# mk3-schield-samtec-vias.net
KiCad netlist of a schematic drawn in EAGLE
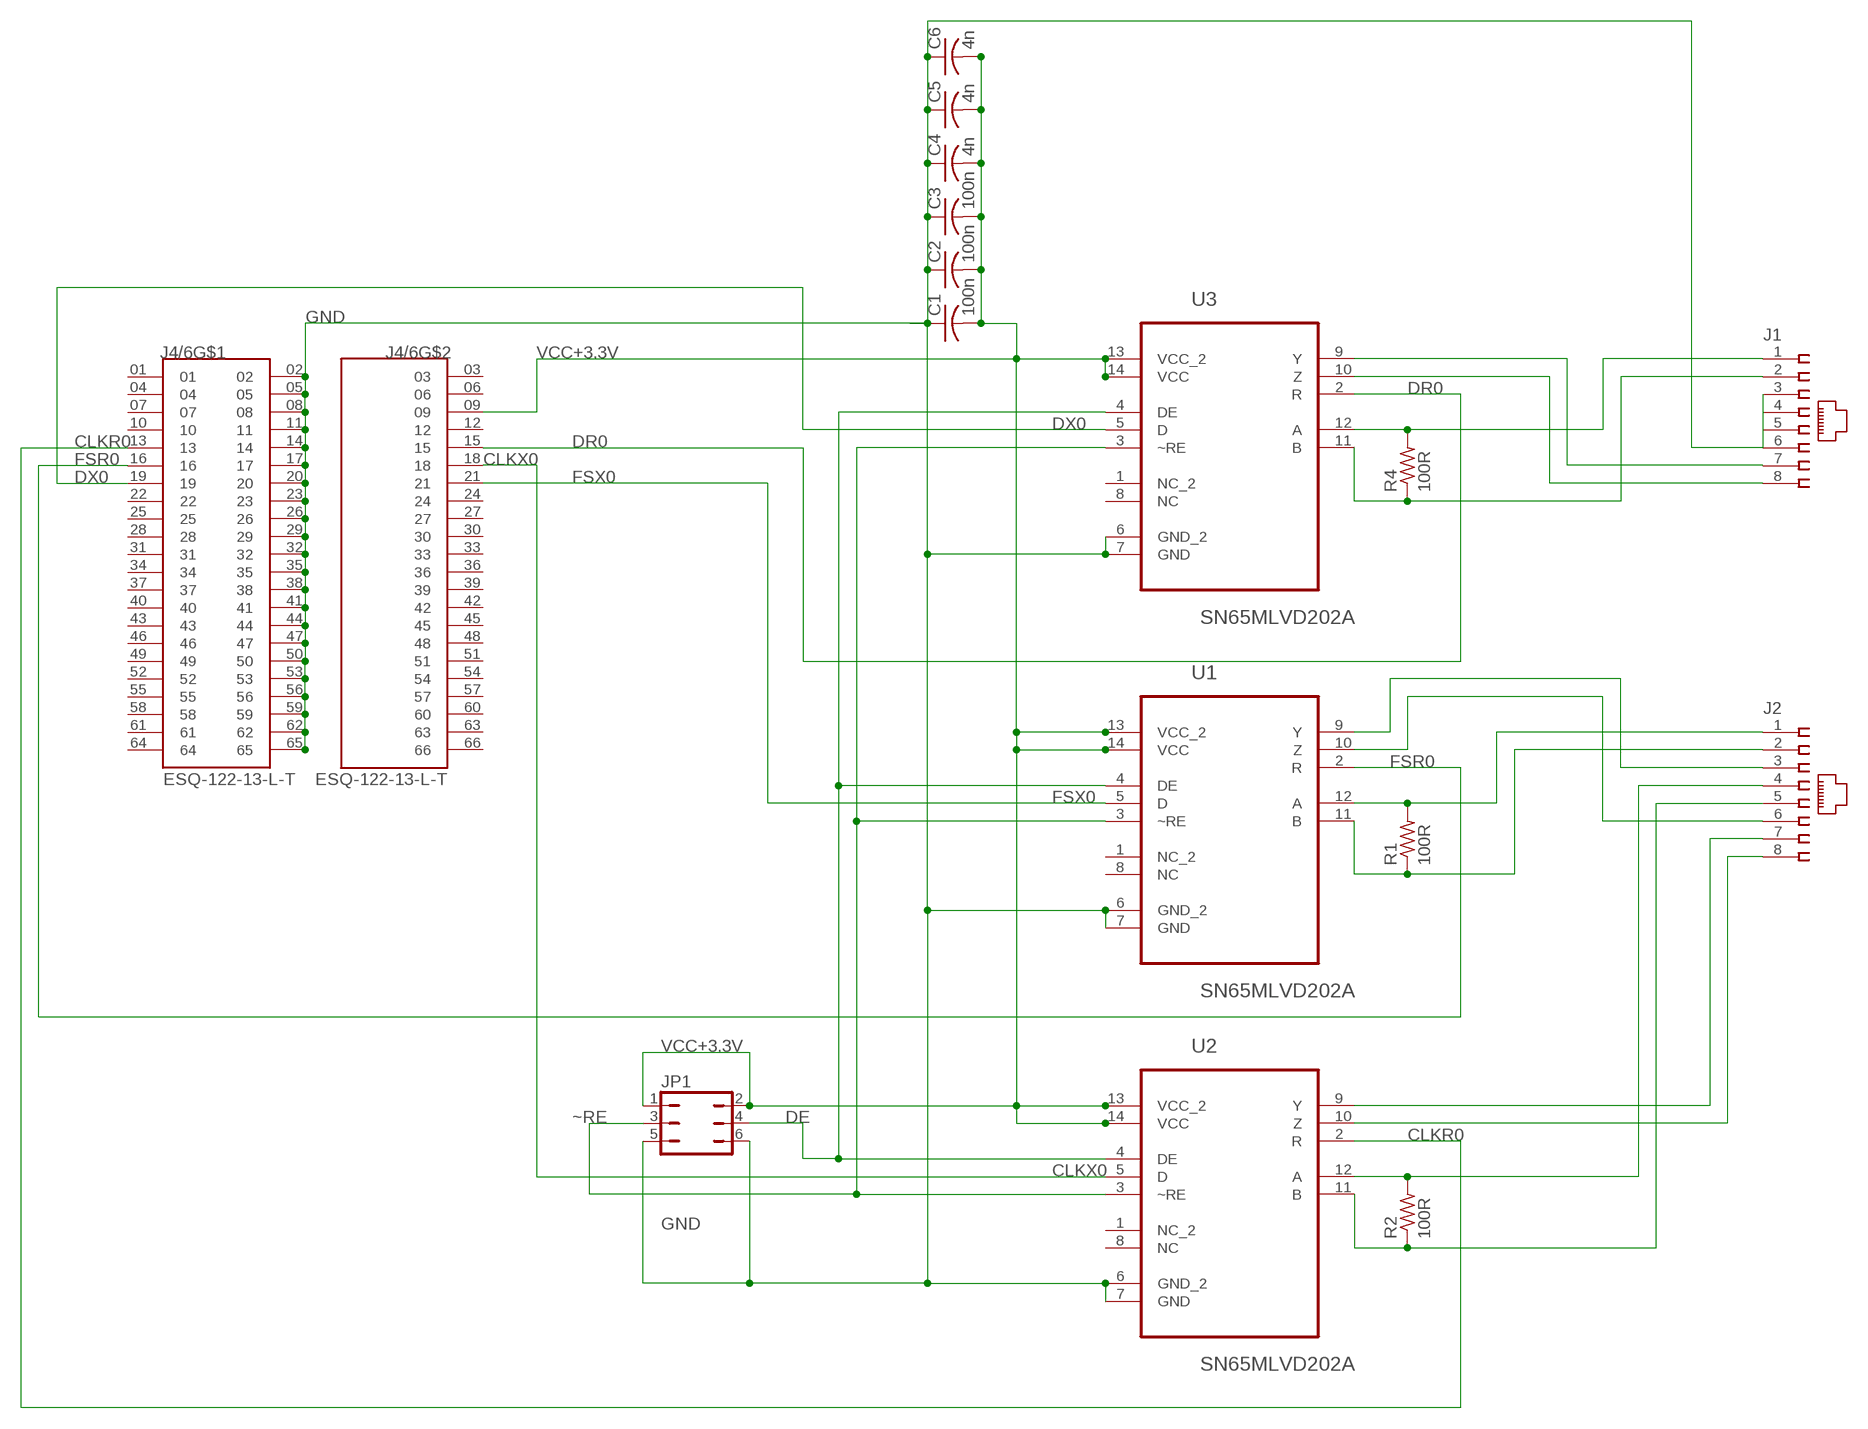
[diagram p0: schematic, sheet 1]

(export (version "E")
  (design (tool "Eeschema 10.0.6"))
  (components
    (comp (ref "C1")
      (value "100n")
      (footprint "eagle-import:C0805")
      (libsource (lib "eagle-import") (part "C-USC0805"))
    )
    (comp (ref "C2")
      (value "100n")
      (footprint "eagle-import:C0805")
      (libsource (lib "eagle-import") (part "C-USC0805"))
    )
    (comp (ref "C3")
      (value "100n")
      (footprint "eagle-import:C0805")
      (libsource (lib "eagle-import") (part "C-USC0805"))
    )
    (comp (ref "C4")
      (value "4n")
      (footprint "eagle-import:C0805")
      (libsource (lib "eagle-import") (part "C-USC0805"))
    )
    (comp (ref "C5")
      (value "4n")
      (footprint "eagle-import:C0805")
      (libsource (lib "eagle-import") (part "C-USC0805"))
    )
    (comp (ref "C6")
      (value "4n")
      (footprint "eagle-import:C0805")
      (libsource (lib "eagle-import") (part "C-USC0805"))
    )
    (comp (ref "J1")
      (value "557785-1-SHIELD")
      (footprint "eagle-import:557785-1")
      (libsource (lib "eagle-import") (part "557785-1-SHIELD"))
    )
    (comp (ref "J2")
      (value "557785-1-SHIELD")
      (footprint "eagle-import:557785-1")
      (libsource (lib "eagle-import") (part "557785-1-SHIELD"))
    )
    (comp (ref "J4/6")
      (value "ESQ-122-13-L-T")
      (footprint "eagle-import:SAMTEC_ESQ-122-13-L-T")
      (fields (field (name "MANUFACTURER") "Samtec"))
      (libsource (lib "eagle-import") (part "ESQ-122-13-L-T"))
    )
    (comp (ref "JP1")
      (value "JP3Q")
      (footprint "eagle-import:JP3Q")
      (libsource (lib "eagle-import") (part "JP3Q"))
    )
    (comp (ref "R1")
      (value "100R")
      (footprint "eagle-import:R0402")
      (libsource (lib "eagle-import") (part "R-US_R0402"))
    )
    (comp (ref "R2")
      (value "100R")
      (footprint "eagle-import:R0402")
      (libsource (lib "eagle-import") (part "R-US_R0402"))
    )
    (comp (ref "R4")
      (value "100R")
      (footprint "eagle-import:R0402")
      (libsource (lib "eagle-import") (part "R-US_R0402"))
    )
    (comp (ref "U1")
      (value "SN65MLVD202A")
      (footprint "eagle-import:SOIC127P600X175-14N")
      (fields (field (name "MPN") "SN65MLVD205AD"))
      (libsource (lib "eagle-import") (part "SN65MLVD205AD"))
    )
    (comp (ref "U2")
      (value "SN65MLVD202A")
      (footprint "eagle-import:SOIC127P600X175-14N")
      (fields (field (name "MPN") "SN65MLVD205AD"))
      (libsource (lib "eagle-import") (part "SN65MLVD205AD"))
    )
    (comp (ref "U3")
      (value "SN65MLVD202A")
      (footprint "eagle-import:SOIC127P600X175-14N")
      (fields (field (name "MPN") "SN65MLVD205AD"))
      (libsource (lib "eagle-import") (part "SN65MLVD205AD"))
    )
  )
  (nets
    (net (code "1") (name "/CLKR0") (class "Default")
      (node (ref "J4/6") (pin "13") (pinfunction "13_13") (pintype "passive"))
      (node (ref "U2") (pin "2") (pinfunction "R_2") (pintype "output"))
    )
    (net (code "2") (name "/CLKX0") (class "Default")
      (node (ref "J4/6") (pin "18") (pinfunction "18_18") (pintype "passive"))
      (node (ref "U2") (pin "5") (pinfunction "D_5") (pintype "input"))
    )
    (net (code "3") (name "/DE") (class "Default")
      (node (ref "JP1") (pin "4") (pinfunction "4_4") (pintype "passive"))
      (node (ref "U1") (pin "4") (pinfunction "DE_4") (pintype "input"))
      (node (ref "U2") (pin "4") (pinfunction "DE_4") (pintype "input"))
      (node (ref "U3") (pin "4") (pinfunction "DE_4") (pintype "input"))
    )
    (net (code "4") (name "/DR0") (class "Default")
      (node (ref "J4/6") (pin "15") (pinfunction "15_15") (pintype "passive"))
      (node (ref "U3") (pin "2") (pinfunction "R_2") (pintype "output"))
    )
    (net (code "5") (name "/DX0") (class "Default")
      (node (ref "J4/6") (pin "19") (pinfunction "19_19") (pintype "passive"))
      (node (ref "U3") (pin "5") (pinfunction "D_5") (pintype "input"))
    )
    (net (code "6") (name "/FSR0") (class "Default")
      (node (ref "J4/6") (pin "16") (pinfunction "16_16") (pintype "passive"))
      (node (ref "U1") (pin "2") (pinfunction "R_2") (pintype "output"))
    )
    (net (code "7") (name "/FSX0") (class "Default")
      (node (ref "J4/6") (pin "21") (pinfunction "21_21") (pintype "passive"))
      (node (ref "U1") (pin "5") (pinfunction "D_5") (pintype "input"))
    )
    (net (code "8") (name "/GND") (class "Default")
      (node (ref "C1") (pin "1") (pinfunction "1_1") (pintype "passive"))
      (node (ref "C2") (pin "1") (pinfunction "1_1") (pintype "passive"))
      (node (ref "C3") (pin "1") (pinfunction "1_1") (pintype "passive"))
      (node (ref "C4") (pin "1") (pinfunction "1_1") (pintype "passive"))
      (node (ref "C5") (pin "1") (pinfunction "1_1") (pintype "passive"))
      (node (ref "C6") (pin "1") (pinfunction "1_1") (pintype "passive"))
      (node (ref "J1") (pin "3") (pinfunction "3_3") (pintype "passive"))
      (node (ref "J1") (pin "4") (pinfunction "4_4") (pintype "passive"))
      (node (ref "J1") (pin "5") (pinfunction "5_5") (pintype "passive"))
      (node (ref "J1") (pin "6") (pinfunction "6_6") (pintype "passive"))
      (node (ref "J4/6") (pin "02") (pinfunction "02_02") (pintype "passive"))
      (node (ref "J4/6") (pin "05") (pinfunction "05_05") (pintype "passive"))
      (node (ref "J4/6") (pin "08") (pinfunction "08_08") (pintype "passive"))
      (node (ref "J4/6") (pin "11") (pinfunction "11_11") (pintype "passive"))
      (node (ref "J4/6") (pin "14") (pinfunction "14_14") (pintype "passive"))
      (node (ref "J4/6") (pin "17") (pinfunction "17_17") (pintype "passive"))
      (node (ref "J4/6") (pin "20") (pinfunction "20_20") (pintype "passive"))
      (node (ref "J4/6") (pin "23") (pinfunction "23_23") (pintype "passive"))
      (node (ref "J4/6") (pin "26") (pinfunction "26_26") (pintype "passive"))
      (node (ref "J4/6") (pin "29") (pinfunction "29_29") (pintype "passive"))
      (node (ref "J4/6") (pin "32") (pinfunction "32_32") (pintype "passive"))
      (node (ref "J4/6") (pin "35") (pinfunction "35_35") (pintype "passive"))
      (node (ref "J4/6") (pin "38") (pinfunction "38_38") (pintype "passive"))
      (node (ref "J4/6") (pin "41") (pinfunction "41_41") (pintype "passive"))
      (node (ref "J4/6") (pin "44") (pinfunction "44_44") (pintype "passive"))
      (node (ref "J4/6") (pin "47") (pinfunction "47_47") (pintype "passive"))
      (node (ref "J4/6") (pin "50") (pinfunction "50_50") (pintype "passive"))
      (node (ref "J4/6") (pin "53") (pinfunction "53_53") (pintype "passive"))
      (node (ref "J4/6") (pin "56") (pinfunction "56_56") (pintype "passive"))
      (node (ref "J4/6") (pin "59") (pinfunction "59_59") (pintype "passive"))
      (node (ref "J4/6") (pin "62") (pinfunction "62_62") (pintype "passive"))
      (node (ref "J4/6") (pin "65") (pinfunction "65_65") (pintype "passive"))
      (node (ref "JP1") (pin "5") (pinfunction "5_5") (pintype "passive"))
      (node (ref "JP1") (pin "6") (pinfunction "6_6") (pintype "passive"))
      (node (ref "U1") (pin "6") (pinfunction "GND_2_6") (pintype "passive"))
      (node (ref "U1") (pin "7") (pinfunction "GND_7") (pintype "passive"))
      (node (ref "U2") (pin "6") (pinfunction "GND_2_6") (pintype "passive"))
      (node (ref "U2") (pin "7") (pinfunction "GND_7") (pintype "passive"))
      (node (ref "U3") (pin "6") (pinfunction "GND_2_6") (pintype "passive"))
      (node (ref "U3") (pin "7") (pinfunction "GND_7") (pintype "passive"))
    )
    (net (code "9") (name "/VCC+3.3V") (class "Default")
      (node (ref "C1") (pin "2") (pinfunction "2_2") (pintype "passive"))
      (node (ref "C2") (pin "2") (pinfunction "2_2") (pintype "passive"))
      (node (ref "C3") (pin "2") (pinfunction "2_2") (pintype "passive"))
      (node (ref "C4") (pin "2") (pinfunction "2_2") (pintype "passive"))
      (node (ref "C5") (pin "2") (pinfunction "2_2") (pintype "passive"))
      (node (ref "C6") (pin "2") (pinfunction "2_2") (pintype "passive"))
      (node (ref "J4/6") (pin "09") (pinfunction "09_09") (pintype "passive"))
      (node (ref "JP1") (pin "1") (pinfunction "1_1") (pintype "passive"))
      (node (ref "JP1") (pin "2") (pinfunction "2_2") (pintype "passive"))
      (node (ref "U1") (pin "13") (pinfunction "VCC_2_13") (pintype "power_in"))
      (node (ref "U1") (pin "14") (pinfunction "VCC_14") (pintype "power_in"))
      (node (ref "U2") (pin "13") (pinfunction "VCC_2_13") (pintype "power_in"))
      (node (ref "U2") (pin "14") (pinfunction "VCC_14") (pintype "power_in"))
      (node (ref "U3") (pin "13") (pinfunction "VCC_2_13") (pintype "power_in"))
      (node (ref "U3") (pin "14") (pinfunction "VCC_14") (pintype "power_in"))
    )
    (net (code "10") (name "/~{RE}") (class "Default")
      (node (ref "JP1") (pin "3") (pinfunction "3_3") (pintype "passive"))
      (node (ref "U1") (pin "3") (pinfunction "~{RE}_3") (pintype "input"))
      (node (ref "U2") (pin "3") (pinfunction "~{RE}_3") (pintype "input"))
      (node (ref "U3") (pin "3") (pinfunction "~{RE}_3") (pintype "input"))
    )
    (net (code "11") (name "Net-(U1-A)") (class "Default")
      (node (ref "J2") (pin "1") (pinfunction "1_1") (pintype "passive"))
      (node (ref "R1") (pin "2") (pinfunction "2_2") (pintype "passive"))
      (node (ref "U1") (pin "12") (pinfunction "A_12") (pintype "output"))
    )
    (net (code "12") (name "Net-(U1-B)") (class "Default")
      (node (ref "J2") (pin "2") (pinfunction "2_2") (pintype "passive"))
      (node (ref "R1") (pin "1") (pinfunction "1_1") (pintype "passive"))
      (node (ref "U1") (pin "11") (pinfunction "B_11") (pintype "output"))
    )
    (net (code "13") (name "Net-(U1-Y)") (class "Default")
      (node (ref "J2") (pin "3") (pinfunction "3_3") (pintype "passive"))
      (node (ref "U1") (pin "9") (pinfunction "Y_9") (pintype "output"))
    )
    (net (code "14") (name "Net-(U1-Z)") (class "Default")
      (node (ref "J2") (pin "6") (pinfunction "6_6") (pintype "passive"))
      (node (ref "U1") (pin "10") (pinfunction "Z_10") (pintype "output"))
    )
    (net (code "15") (name "Net-(U2-A)") (class "Default")
      (node (ref "J2") (pin "4") (pinfunction "4_4") (pintype "passive"))
      (node (ref "R2") (pin "2") (pinfunction "2_2") (pintype "passive"))
      (node (ref "U2") (pin "12") (pinfunction "A_12") (pintype "output"))
    )
    (net (code "16") (name "Net-(U2-B)") (class "Default")
      (node (ref "J2") (pin "5") (pinfunction "5_5") (pintype "passive"))
      (node (ref "R2") (pin "1") (pinfunction "1_1") (pintype "passive"))
      (node (ref "U2") (pin "11") (pinfunction "B_11") (pintype "output"))
    )
    (net (code "17") (name "Net-(U2-Y)") (class "Default")
      (node (ref "J2") (pin "7") (pinfunction "7_7") (pintype "passive"))
      (node (ref "U2") (pin "9") (pinfunction "Y_9") (pintype "output"))
    )
    (net (code "18") (name "Net-(U2-Z)") (class "Default")
      (node (ref "J2") (pin "8") (pinfunction "8_8") (pintype "passive"))
      (node (ref "U2") (pin "10") (pinfunction "Z_10") (pintype "output"))
    )
    (net (code "19") (name "Net-(U3-A)") (class "Default")
      (node (ref "J1") (pin "1") (pinfunction "1_1") (pintype "passive"))
      (node (ref "R4") (pin "2") (pinfunction "2_2") (pintype "passive"))
      (node (ref "U3") (pin "12") (pinfunction "A_12") (pintype "output"))
    )
    (net (code "20") (name "Net-(U3-B)") (class "Default")
      (node (ref "J1") (pin "2") (pinfunction "2_2") (pintype "passive"))
      (node (ref "R4") (pin "1") (pinfunction "1_1") (pintype "passive"))
      (node (ref "U3") (pin "11") (pinfunction "B_11") (pintype "output"))
    )
    (net (code "21") (name "Net-(U3-Y)") (class "Default")
      (node (ref "J1") (pin "7") (pinfunction "7_7") (pintype "passive"))
      (node (ref "U3") (pin "9") (pinfunction "Y_9") (pintype "output"))
    )
    (net (code "22") (name "Net-(U3-Z)") (class "Default")
      (node (ref "J1") (pin "8") (pinfunction "8_8") (pintype "passive"))
      (node (ref "U3") (pin "10") (pinfunction "Z_10") (pintype "output"))
    )
    (net (code "23") (name "unconnected-(J4/6-Pad01)") (class "Default")
      (node (ref "J4/6") (pin "01") (pinfunction "01_01") (pintype "passive"))
    )
    (net (code "24") (name "unconnected-(J4/6-Pad03)") (class "Default")
      (node (ref "J4/6") (pin "03") (pinfunction "03_03") (pintype "passive"))
    )
    (net (code "25") (name "unconnected-(J4/6-Pad04)") (class "Default")
      (node (ref "J4/6") (pin "04") (pinfunction "04_04") (pintype "passive"))
    )
    (net (code "26") (name "unconnected-(J4/6-Pad06)") (class "Default")
      (node (ref "J4/6") (pin "06") (pinfunction "06_06") (pintype "passive"))
    )
    (net (code "27") (name "unconnected-(J4/6-Pad07)") (class "Default")
      (node (ref "J4/6") (pin "07") (pinfunction "07_07") (pintype "passive"))
    )
    (net (code "28") (name "unconnected-(J4/6-Pad10)") (class "Default")
      (node (ref "J4/6") (pin "10") (pinfunction "10_10") (pintype "passive"))
    )
    (net (code "29") (name "unconnected-(J4/6-Pad12)") (class "Default")
      (node (ref "J4/6") (pin "12") (pinfunction "12_12") (pintype "passive"))
    )
    (net (code "30") (name "unconnected-(J4/6-Pad22)") (class "Default")
      (node (ref "J4/6") (pin "22") (pinfunction "22_22") (pintype "passive"))
    )
    (net (code "31") (name "unconnected-(J4/6-Pad24)") (class "Default")
      (node (ref "J4/6") (pin "24") (pinfunction "24_24") (pintype "passive"))
    )
    (net (code "32") (name "unconnected-(J4/6-Pad25)") (class "Default")
      (node (ref "J4/6") (pin "25") (pinfunction "25_25") (pintype "passive"))
    )
    (net (code "33") (name "unconnected-(J4/6-Pad27)") (class "Default")
      (node (ref "J4/6") (pin "27") (pinfunction "27_27") (pintype "passive"))
    )
    (net (code "34") (name "unconnected-(J4/6-Pad28)") (class "Default")
      (node (ref "J4/6") (pin "28") (pinfunction "28_28") (pintype "passive"))
    )
    (net (code "35") (name "unconnected-(J4/6-Pad30)") (class "Default")
      (node (ref "J4/6") (pin "30") (pinfunction "30_30") (pintype "passive"))
    )
    (net (code "36") (name "unconnected-(J4/6-Pad31)") (class "Default")
      (node (ref "J4/6") (pin "31") (pinfunction "31_31") (pintype "passive"))
    )
    (net (code "37") (name "unconnected-(J4/6-Pad33)") (class "Default")
      (node (ref "J4/6") (pin "33") (pinfunction "33_33") (pintype "passive"))
    )
    (net (code "38") (name "unconnected-(J4/6-Pad34)") (class "Default")
      (node (ref "J4/6") (pin "34") (pinfunction "34_34") (pintype "passive"))
    )
    (net (code "39") (name "unconnected-(J4/6-Pad36)") (class "Default")
      (node (ref "J4/6") (pin "36") (pinfunction "36_36") (pintype "passive"))
    )
    (net (code "40") (name "unconnected-(J4/6-Pad37)") (class "Default")
      (node (ref "J4/6") (pin "37") (pinfunction "37_37") (pintype "passive"))
    )
    (net (code "41") (name "unconnected-(J4/6-Pad39)") (class "Default")
      (node (ref "J4/6") (pin "39") (pinfunction "39_39") (pintype "passive"))
    )
    (net (code "42") (name "unconnected-(J4/6-Pad40)") (class "Default")
      (node (ref "J4/6") (pin "40") (pinfunction "40_40") (pintype "passive"))
    )
    (net (code "43") (name "unconnected-(J4/6-Pad42)") (class "Default")
      (node (ref "J4/6") (pin "42") (pinfunction "42_42") (pintype "passive"))
    )
    (net (code "44") (name "unconnected-(J4/6-Pad43)") (class "Default")
      (node (ref "J4/6") (pin "43") (pinfunction "43_43") (pintype "passive"))
    )
    (net (code "45") (name "unconnected-(J4/6-Pad45)") (class "Default")
      (node (ref "J4/6") (pin "45") (pinfunction "45_45") (pintype "passive"))
    )
    (net (code "46") (name "unconnected-(J4/6-Pad46)") (class "Default")
      (node (ref "J4/6") (pin "46") (pinfunction "46_46") (pintype "passive"))
    )
    (net (code "47") (name "unconnected-(J4/6-Pad48)") (class "Default")
      (node (ref "J4/6") (pin "48") (pinfunction "48_48") (pintype "passive"))
    )
    (net (code "48") (name "unconnected-(J4/6-Pad49)") (class "Default")
      (node (ref "J4/6") (pin "49") (pinfunction "49_49") (pintype "passive"))
    )
    (net (code "49") (name "unconnected-(J4/6-Pad51)") (class "Default")
      (node (ref "J4/6") (pin "51") (pinfunction "51_51") (pintype "passive"))
    )
    (net (code "50") (name "unconnected-(J4/6-Pad52)") (class "Default")
      (node (ref "J4/6") (pin "52") (pinfunction "52_52") (pintype "passive"))
    )
    (net (code "51") (name "unconnected-(J4/6-Pad54)") (class "Default")
      (node (ref "J4/6") (pin "54") (pinfunction "54_54") (pintype "passive"))
    )
    (net (code "52") (name "unconnected-(J4/6-Pad55)") (class "Default")
      (node (ref "J4/6") (pin "55") (pinfunction "55_55") (pintype "passive"))
    )
    (net (code "53") (name "unconnected-(J4/6-Pad57)") (class "Default")
      (node (ref "J4/6") (pin "57") (pinfunction "57_57") (pintype "passive"))
    )
    (net (code "54") (name "unconnected-(J4/6-Pad58)") (class "Default")
      (node (ref "J4/6") (pin "58") (pinfunction "58_58") (pintype "passive"))
    )
    (net (code "55") (name "unconnected-(J4/6-Pad60)") (class "Default")
      (node (ref "J4/6") (pin "60") (pinfunction "60_60") (pintype "passive"))
    )
    (net (code "56") (name "unconnected-(J4/6-Pad61)") (class "Default")
      (node (ref "J4/6") (pin "61") (pinfunction "61_61") (pintype "passive"))
    )
    (net (code "57") (name "unconnected-(J4/6-Pad63)") (class "Default")
      (node (ref "J4/6") (pin "63") (pinfunction "63_63") (pintype "passive"))
    )
    (net (code "58") (name "unconnected-(J4/6-Pad64)") (class "Default")
      (node (ref "J4/6") (pin "64") (pinfunction "64_64") (pintype "passive"))
    )
    (net (code "59") (name "unconnected-(J4/6-Pad66)") (class "Default")
      (node (ref "J4/6") (pin "66") (pinfunction "66_66") (pintype "passive"))
    )
    (net (code "60") (name "unconnected-(U1-NC-Pad8)") (class "Default")
      (node (ref "U1") (pin "8") (pinfunction "NC_8") (pintype "no_connect"))
    )
    (net (code "61") (name "unconnected-(U1-NC_2-Pad1)") (class "Default")
      (node (ref "U1") (pin "1") (pinfunction "NC_2_1") (pintype "no_connect"))
    )
    (net (code "62") (name "unconnected-(U2-NC-Pad8)") (class "Default")
      (node (ref "U2") (pin "8") (pinfunction "NC_8") (pintype "no_connect"))
    )
    (net (code "63") (name "unconnected-(U2-NC_2-Pad1)") (class "Default")
      (node (ref "U2") (pin "1") (pinfunction "NC_2_1") (pintype "no_connect"))
    )
    (net (code "64") (name "unconnected-(U3-NC-Pad8)") (class "Default")
      (node (ref "U3") (pin "8") (pinfunction "NC_8") (pintype "no_connect"))
    )
    (net (code "65") (name "unconnected-(U3-NC_2-Pad1)") (class "Default")
      (node (ref "U3") (pin "1") (pinfunction "NC_2_1") (pintype "no_connect"))
    )
  )
)
